# breakout.net
KiCad netlist of a schematic drawn in EAGLE
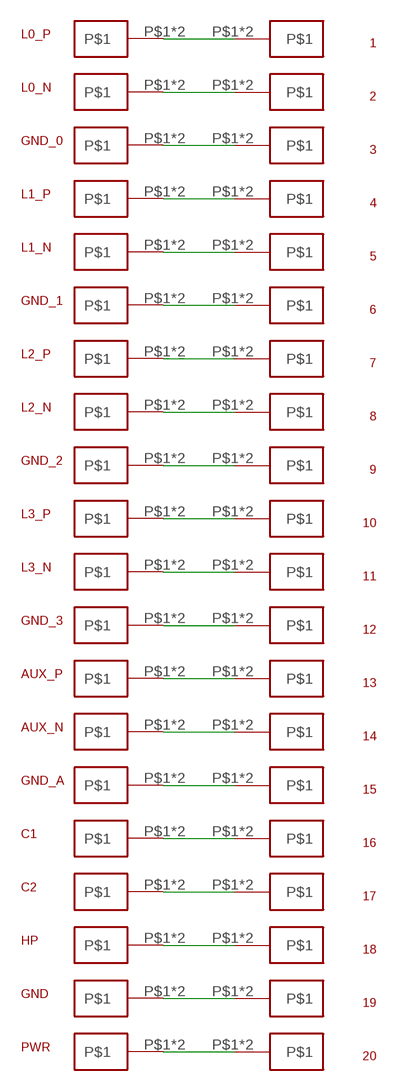
[diagram p0: schematic, sheet 1]

(export (version "E")
  (design (tool "Eeschema 10.0.6"))
  (components
    (comp (ref "1")
      (value "30_AWG_PAD")
      (footprint "eagle-import:30_AWG_PAD")
      (libsource (lib "eagle-import") (part "30_AWG_PAD"))
    )
    (comp (ref "2")
      (value "30_AWG_PAD")
      (footprint "eagle-import:30_AWG_PAD")
      (libsource (lib "eagle-import") (part "30_AWG_PAD"))
    )
    (comp (ref "3")
      (value "30_AWG_PAD")
      (footprint "eagle-import:30_AWG_PAD")
      (libsource (lib "eagle-import") (part "30_AWG_PAD"))
    )
    (comp (ref "4")
      (value "30_AWG_PAD")
      (footprint "eagle-import:30_AWG_PAD")
      (libsource (lib "eagle-import") (part "30_AWG_PAD"))
    )
    (comp (ref "5")
      (value "30_AWG_PAD")
      (footprint "eagle-import:30_AWG_PAD")
      (libsource (lib "eagle-import") (part "30_AWG_PAD"))
    )
    (comp (ref "6")
      (value "30_AWG_PAD")
      (footprint "eagle-import:30_AWG_PAD")
      (libsource (lib "eagle-import") (part "30_AWG_PAD"))
    )
    (comp (ref "7")
      (value "30_AWG_PAD")
      (footprint "eagle-import:30_AWG_PAD")
      (libsource (lib "eagle-import") (part "30_AWG_PAD"))
    )
    (comp (ref "8")
      (value "30_AWG_PAD")
      (footprint "eagle-import:30_AWG_PAD")
      (libsource (lib "eagle-import") (part "30_AWG_PAD"))
    )
    (comp (ref "9")
      (value "30_AWG_PAD")
      (footprint "eagle-import:30_AWG_PAD")
      (libsource (lib "eagle-import") (part "30_AWG_PAD"))
    )
    (comp (ref "10")
      (value "30_AWG_PAD")
      (footprint "eagle-import:30_AWG_PAD")
      (libsource (lib "eagle-import") (part "30_AWG_PAD"))
    )
    (comp (ref "11")
      (value "30_AWG_PAD")
      (footprint "eagle-import:30_AWG_PAD")
      (libsource (lib "eagle-import") (part "30_AWG_PAD"))
    )
    (comp (ref "12")
      (value "30_AWG_PAD")
      (footprint "eagle-import:30_AWG_PAD")
      (libsource (lib "eagle-import") (part "30_AWG_PAD"))
    )
    (comp (ref "13")
      (value "30_AWG_PAD")
      (footprint "eagle-import:30_AWG_PAD")
      (libsource (lib "eagle-import") (part "30_AWG_PAD"))
    )
    (comp (ref "14")
      (value "30_AWG_PAD")
      (footprint "eagle-import:30_AWG_PAD")
      (libsource (lib "eagle-import") (part "30_AWG_PAD"))
    )
    (comp (ref "15")
      (value "30_AWG_PAD")
      (footprint "eagle-import:30_AWG_PAD")
      (libsource (lib "eagle-import") (part "30_AWG_PAD"))
    )
    (comp (ref "16")
      (value "30_AWG_PAD")
      (footprint "eagle-import:30_AWG_PAD")
      (libsource (lib "eagle-import") (part "30_AWG_PAD"))
    )
    (comp (ref "17")
      (value "30_AWG_PAD")
      (footprint "eagle-import:30_AWG_PAD")
      (libsource (lib "eagle-import") (part "30_AWG_PAD"))
    )
    (comp (ref "18")
      (value "30_AWG_PAD")
      (footprint "eagle-import:30_AWG_PAD")
      (libsource (lib "eagle-import") (part "30_AWG_PAD"))
    )
    (comp (ref "19")
      (value "30_AWG_PAD")
      (footprint "eagle-import:30_AWG_PAD")
      (libsource (lib "eagle-import") (part "30_AWG_PAD"))
    )
    (comp (ref "20")
      (value "30_AWG_PAD")
      (footprint "eagle-import:30_AWG_PAD")
      (libsource (lib "eagle-import") (part "30_AWG_PAD"))
    )
    (comp (ref "AUX_N")
      (value "30_AWG_PAD")
      (footprint "eagle-import:30_AWG_PAD")
      (libsource (lib "eagle-import") (part "30_AWG_PAD"))
    )
    (comp (ref "AUX_P")
      (value "30_AWG_PAD")
      (footprint "eagle-import:30_AWG_PAD")
      (libsource (lib "eagle-import") (part "30_AWG_PAD"))
    )
    (comp (ref "C1")
      (value "30_AWG_PAD")
      (footprint "eagle-import:30_AWG_PAD")
      (libsource (lib "eagle-import") (part "30_AWG_PAD"))
    )
    (comp (ref "C2")
      (value "30_AWG_PAD")
      (footprint "eagle-import:30_AWG_PAD")
      (libsource (lib "eagle-import") (part "30_AWG_PAD"))
    )
    (comp (ref "GND")
      (value "30_AWG_PAD")
      (footprint "eagle-import:30_AWG_PAD")
      (libsource (lib "eagle-import") (part "30_AWG_PAD"))
    )
    (comp (ref "GND_0")
      (value "30_AWG_PAD")
      (footprint "eagle-import:30_AWG_PAD")
      (libsource (lib "eagle-import") (part "30_AWG_PAD"))
    )
    (comp (ref "GND_1")
      (value "30_AWG_PAD")
      (footprint "eagle-import:30_AWG_PAD")
      (libsource (lib "eagle-import") (part "30_AWG_PAD"))
    )
    (comp (ref "GND_2")
      (value "30_AWG_PAD")
      (footprint "eagle-import:30_AWG_PAD")
      (libsource (lib "eagle-import") (part "30_AWG_PAD"))
    )
    (comp (ref "GND_3")
      (value "30_AWG_PAD")
      (footprint "eagle-import:30_AWG_PAD")
      (libsource (lib "eagle-import") (part "30_AWG_PAD"))
    )
    (comp (ref "GND_A")
      (value "30_AWG_PAD")
      (footprint "eagle-import:30_AWG_PAD")
      (libsource (lib "eagle-import") (part "30_AWG_PAD"))
    )
    (comp (ref "HP")
      (value "30_AWG_PAD")
      (footprint "eagle-import:30_AWG_PAD")
      (libsource (lib "eagle-import") (part "30_AWG_PAD"))
    )
    (comp (ref "L0_N")
      (value "30_AWG_PAD")
      (footprint "eagle-import:30_AWG_PAD")
      (libsource (lib "eagle-import") (part "30_AWG_PAD"))
    )
    (comp (ref "L0_P")
      (value "30_AWG_PAD")
      (footprint "eagle-import:30_AWG_PAD")
      (libsource (lib "eagle-import") (part "30_AWG_PAD"))
    )
    (comp (ref "L1_N")
      (value "30_AWG_PAD")
      (footprint "eagle-import:30_AWG_PAD")
      (libsource (lib "eagle-import") (part "30_AWG_PAD"))
    )
    (comp (ref "L1_P")
      (value "30_AWG_PAD")
      (footprint "eagle-import:30_AWG_PAD")
      (libsource (lib "eagle-import") (part "30_AWG_PAD"))
    )
    (comp (ref "L2_N")
      (value "30_AWG_PAD")
      (footprint "eagle-import:30_AWG_PAD")
      (libsource (lib "eagle-import") (part "30_AWG_PAD"))
    )
    (comp (ref "L2_P")
      (value "30_AWG_PAD")
      (footprint "eagle-import:30_AWG_PAD")
      (libsource (lib "eagle-import") (part "30_AWG_PAD"))
    )
    (comp (ref "L3_N")
      (value "30_AWG_PAD")
      (footprint "eagle-import:30_AWG_PAD")
      (libsource (lib "eagle-import") (part "30_AWG_PAD"))
    )
    (comp (ref "L3_P")
      (value "30_AWG_PAD")
      (footprint "eagle-import:30_AWG_PAD")
      (libsource (lib "eagle-import") (part "30_AWG_PAD"))
    )
    (comp (ref "PWR")
      (value "30_AWG_PAD")
      (footprint "eagle-import:30_AWG_PAD")
      (libsource (lib "eagle-import") (part "30_AWG_PAD"))
    )
  )
  (nets
    (net (code "1") (name "Net-(1-P$1-PadP$2)") (class "Default")
      (node (ref "1") (pin "P$1") (pinfunction "P$1_P$1") (pintype "bidirectional"))
      (node (ref "1") (pin "P$2") (pinfunction "P$1_P$2") (pintype "bidirectional"))
      (node (ref "L0_P") (pin "P$1") (pinfunction "P$1_P$1") (pintype "bidirectional"))
      (node (ref "L0_P") (pin "P$2") (pinfunction "P$1_P$2") (pintype "bidirectional"))
    )
    (net (code "2") (name "Net-(2-P$1-PadP$2)") (class "Default")
      (node (ref "2") (pin "P$1") (pinfunction "P$1_P$1") (pintype "bidirectional"))
      (node (ref "2") (pin "P$2") (pinfunction "P$1_P$2") (pintype "bidirectional"))
      (node (ref "L0_N") (pin "P$1") (pinfunction "P$1_P$1") (pintype "bidirectional"))
      (node (ref "L0_N") (pin "P$2") (pinfunction "P$1_P$2") (pintype "bidirectional"))
    )
    (net (code "3") (name "Net-(3-P$1-PadP$2)") (class "Default")
      (node (ref "3") (pin "P$1") (pinfunction "P$1_P$1") (pintype "bidirectional"))
      (node (ref "3") (pin "P$2") (pinfunction "P$1_P$2") (pintype "bidirectional"))
      (node (ref "GND_0") (pin "P$1") (pinfunction "P$1_P$1") (pintype "bidirectional"))
      (node (ref "GND_0") (pin "P$2") (pinfunction "P$1_P$2") (pintype "bidirectional"))
    )
    (net (code "4") (name "Net-(4-P$1-PadP$2)") (class "Default")
      (node (ref "4") (pin "P$1") (pinfunction "P$1_P$1") (pintype "bidirectional"))
      (node (ref "4") (pin "P$2") (pinfunction "P$1_P$2") (pintype "bidirectional"))
      (node (ref "L1_P") (pin "P$1") (pinfunction "P$1_P$1") (pintype "bidirectional"))
      (node (ref "L1_P") (pin "P$2") (pinfunction "P$1_P$2") (pintype "bidirectional"))
    )
    (net (code "5") (name "Net-(5-P$1-PadP$2)") (class "Default")
      (node (ref "5") (pin "P$1") (pinfunction "P$1_P$1") (pintype "bidirectional"))
      (node (ref "5") (pin "P$2") (pinfunction "P$1_P$2") (pintype "bidirectional"))
      (node (ref "L1_N") (pin "P$1") (pinfunction "P$1_P$1") (pintype "bidirectional"))
      (node (ref "L1_N") (pin "P$2") (pinfunction "P$1_P$2") (pintype "bidirectional"))
    )
    (net (code "6") (name "Net-(6-P$1-PadP$2)") (class "Default")
      (node (ref "6") (pin "P$1") (pinfunction "P$1_P$1") (pintype "bidirectional"))
      (node (ref "6") (pin "P$2") (pinfunction "P$1_P$2") (pintype "bidirectional"))
      (node (ref "GND_1") (pin "P$1") (pinfunction "P$1_P$1") (pintype "bidirectional"))
      (node (ref "GND_1") (pin "P$2") (pinfunction "P$1_P$2") (pintype "bidirectional"))
    )
    (net (code "7") (name "Net-(7-P$1-PadP$2)") (class "Default")
      (node (ref "7") (pin "P$1") (pinfunction "P$1_P$1") (pintype "bidirectional"))
      (node (ref "7") (pin "P$2") (pinfunction "P$1_P$2") (pintype "bidirectional"))
      (node (ref "L2_P") (pin "P$1") (pinfunction "P$1_P$1") (pintype "bidirectional"))
      (node (ref "L2_P") (pin "P$2") (pinfunction "P$1_P$2") (pintype "bidirectional"))
    )
    (net (code "8") (name "Net-(8-P$1-PadP$2)") (class "Default")
      (node (ref "8") (pin "P$1") (pinfunction "P$1_P$1") (pintype "bidirectional"))
      (node (ref "8") (pin "P$2") (pinfunction "P$1_P$2") (pintype "bidirectional"))
      (node (ref "L2_N") (pin "P$1") (pinfunction "P$1_P$1") (pintype "bidirectional"))
      (node (ref "L2_N") (pin "P$2") (pinfunction "P$1_P$2") (pintype "bidirectional"))
    )
    (net (code "9") (name "Net-(9-P$1-PadP$2)") (class "Default")
      (node (ref "9") (pin "P$1") (pinfunction "P$1_P$1") (pintype "bidirectional"))
      (node (ref "9") (pin "P$2") (pinfunction "P$1_P$2") (pintype "bidirectional"))
      (node (ref "GND_2") (pin "P$1") (pinfunction "P$1_P$1") (pintype "bidirectional"))
      (node (ref "GND_2") (pin "P$2") (pinfunction "P$1_P$2") (pintype "bidirectional"))
    )
    (net (code "10") (name "Net-(10-P$1-PadP$2)") (class "Default")
      (node (ref "10") (pin "P$1") (pinfunction "P$1_P$1") (pintype "bidirectional"))
      (node (ref "10") (pin "P$2") (pinfunction "P$1_P$2") (pintype "bidirectional"))
      (node (ref "L3_P") (pin "P$1") (pinfunction "P$1_P$1") (pintype "bidirectional"))
      (node (ref "L3_P") (pin "P$2") (pinfunction "P$1_P$2") (pintype "bidirectional"))
    )
    (net (code "11") (name "Net-(11-P$1-PadP$2)") (class "Default")
      (node (ref "11") (pin "P$1") (pinfunction "P$1_P$1") (pintype "bidirectional"))
      (node (ref "11") (pin "P$2") (pinfunction "P$1_P$2") (pintype "bidirectional"))
      (node (ref "L3_N") (pin "P$1") (pinfunction "P$1_P$1") (pintype "bidirectional"))
      (node (ref "L3_N") (pin "P$2") (pinfunction "P$1_P$2") (pintype "bidirectional"))
    )
    (net (code "12") (name "Net-(12-P$1-PadP$2)") (class "Default")
      (node (ref "12") (pin "P$1") (pinfunction "P$1_P$1") (pintype "bidirectional"))
      (node (ref "12") (pin "P$2") (pinfunction "P$1_P$2") (pintype "bidirectional"))
      (node (ref "GND_3") (pin "P$1") (pinfunction "P$1_P$1") (pintype "bidirectional"))
      (node (ref "GND_3") (pin "P$2") (pinfunction "P$1_P$2") (pintype "bidirectional"))
    )
    (net (code "13") (name "Net-(13-P$1-PadP$2)") (class "Default")
      (node (ref "13") (pin "P$1") (pinfunction "P$1_P$1") (pintype "bidirectional"))
      (node (ref "13") (pin "P$2") (pinfunction "P$1_P$2") (pintype "bidirectional"))
      (node (ref "AUX_P") (pin "P$1") (pinfunction "P$1_P$1") (pintype "bidirectional"))
      (node (ref "AUX_P") (pin "P$2") (pinfunction "P$1_P$2") (pintype "bidirectional"))
    )
    (net (code "14") (name "Net-(14-P$1-PadP$2)") (class "Default")
      (node (ref "14") (pin "P$1") (pinfunction "P$1_P$1") (pintype "bidirectional"))
      (node (ref "14") (pin "P$2") (pinfunction "P$1_P$2") (pintype "bidirectional"))
      (node (ref "AUX_N") (pin "P$1") (pinfunction "P$1_P$1") (pintype "bidirectional"))
      (node (ref "AUX_N") (pin "P$2") (pinfunction "P$1_P$2") (pintype "bidirectional"))
    )
    (net (code "15") (name "Net-(15-P$1-PadP$2)") (class "Default")
      (node (ref "15") (pin "P$1") (pinfunction "P$1_P$1") (pintype "bidirectional"))
      (node (ref "15") (pin "P$2") (pinfunction "P$1_P$2") (pintype "bidirectional"))
      (node (ref "GND_A") (pin "P$1") (pinfunction "P$1_P$1") (pintype "bidirectional"))
      (node (ref "GND_A") (pin "P$2") (pinfunction "P$1_P$2") (pintype "bidirectional"))
    )
    (net (code "16") (name "Net-(16-P$1-PadP$2)") (class "Default")
      (node (ref "16") (pin "P$1") (pinfunction "P$1_P$1") (pintype "bidirectional"))
      (node (ref "16") (pin "P$2") (pinfunction "P$1_P$2") (pintype "bidirectional"))
      (node (ref "C1") (pin "P$1") (pinfunction "P$1_P$1") (pintype "bidirectional"))
      (node (ref "C1") (pin "P$2") (pinfunction "P$1_P$2") (pintype "bidirectional"))
    )
    (net (code "17") (name "Net-(17-P$1-PadP$2)") (class "Default")
      (node (ref "17") (pin "P$1") (pinfunction "P$1_P$1") (pintype "bidirectional"))
      (node (ref "17") (pin "P$2") (pinfunction "P$1_P$2") (pintype "bidirectional"))
      (node (ref "C2") (pin "P$1") (pinfunction "P$1_P$1") (pintype "bidirectional"))
      (node (ref "C2") (pin "P$2") (pinfunction "P$1_P$2") (pintype "bidirectional"))
    )
    (net (code "18") (name "Net-(18-P$1-PadP$2)") (class "Default")
      (node (ref "18") (pin "P$1") (pinfunction "P$1_P$1") (pintype "bidirectional"))
      (node (ref "18") (pin "P$2") (pinfunction "P$1_P$2") (pintype "bidirectional"))
      (node (ref "HP") (pin "P$1") (pinfunction "P$1_P$1") (pintype "bidirectional"))
      (node (ref "HP") (pin "P$2") (pinfunction "P$1_P$2") (pintype "bidirectional"))
    )
    (net (code "19") (name "Net-(19-P$1-PadP$2)") (class "Default")
      (node (ref "19") (pin "P$1") (pinfunction "P$1_P$1") (pintype "bidirectional"))
      (node (ref "19") (pin "P$2") (pinfunction "P$1_P$2") (pintype "bidirectional"))
      (node (ref "GND") (pin "P$1") (pinfunction "P$1_P$1") (pintype "bidirectional"))
      (node (ref "GND") (pin "P$2") (pinfunction "P$1_P$2") (pintype "bidirectional"))
    )
    (net (code "20") (name "Net-(20-P$1-PadP$2)") (class "Default")
      (node (ref "20") (pin "P$1") (pinfunction "P$1_P$1") (pintype "bidirectional"))
      (node (ref "20") (pin "P$2") (pinfunction "P$1_P$2") (pintype "bidirectional"))
      (node (ref "PWR") (pin "P$1") (pinfunction "P$1_P$1") (pintype "bidirectional"))
      (node (ref "PWR") (pin "P$2") (pinfunction "P$1_P$2") (pintype "bidirectional"))
    )
  )
)
